# Voltage_Regulator.net
KiCad netlist of a schematic drawn in Altium Designer
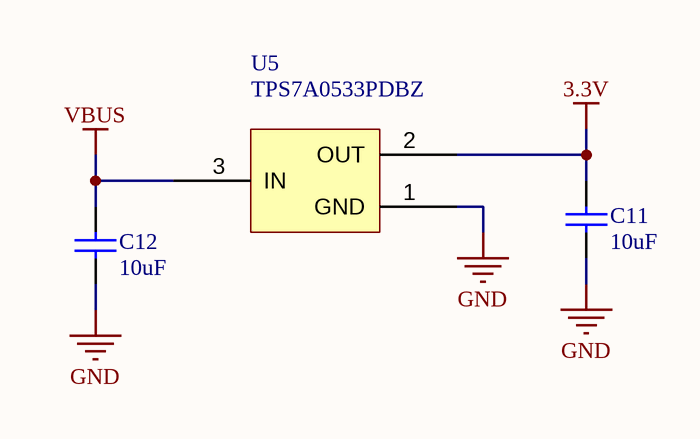
[diagram p0: Voltage Regulator.SchDoc]

(export (version "E")
  (design (tool "Eeschema 10.0.6"))
  (components
    (comp (ref "C11") (value "10uF") (footprint "Capacitor 0603") (libsource (lib "x-io") (part "Capacitor")))
    (comp (ref "C12") (value "10uF") (footprint "Capacitor 0603") (libsource (lib "x-io") (part "Capacitor")))
    (comp (ref "U5")
      (value "TPS7A0533PDBZ")
      (footprint "SOT-23")
      (libsource (lib "x-io") (part "TPS7A0533PDBZ"))
    )
  )
  (nets
    (net (code "1") (name "3.3V") (class "Default")
      (node (ref "C11") (pin "2") (pinfunction "2_2") (pintype "passive"))
      (node (ref "U5") (pin "2") (pinfunction "OUT_2") (pintype "passive"))
    )
    (net (code "2") (name "GND") (class "Default")
      (node (ref "C11") (pin "1") (pinfunction "1_1") (pintype "passive"))
      (node (ref "C12") (pin "1") (pinfunction "1_1") (pintype "passive"))
      (node (ref "U5") (pin "1") (pinfunction "GND_1") (pintype "passive"))
    )
    (net (code "3") (name "VBUS") (class "Default")
      (node (ref "C12") (pin "2") (pinfunction "2_2") (pintype "passive"))
      (node (ref "U5") (pin "3") (pinfunction "IN_3") (pintype "passive"))
    )
  )
)
